# Wifinfo.net
KiCad netlist of a schematic drawn in EAGLE
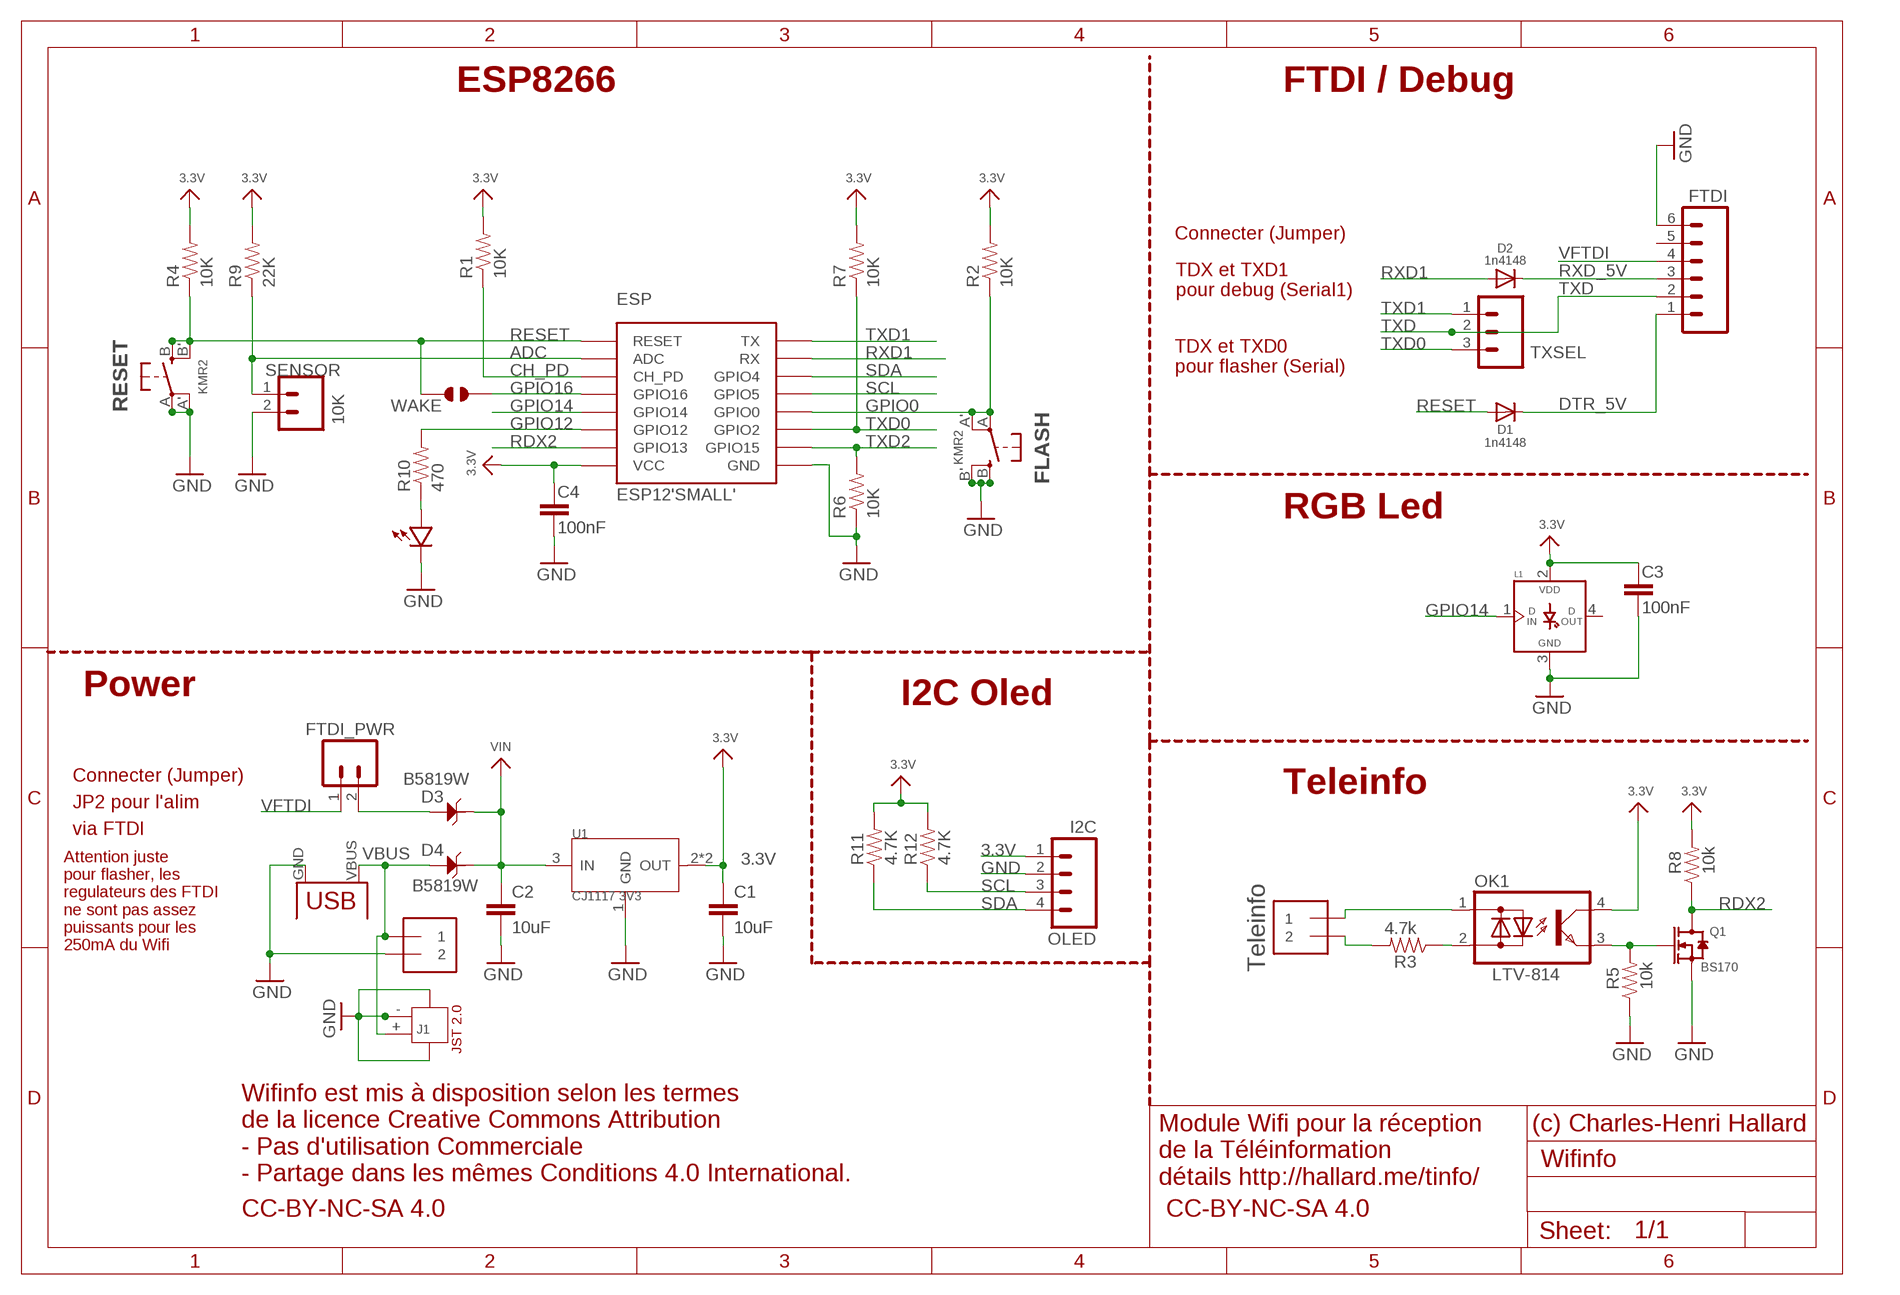
[diagram p0: schematic, sheet 1]

(export (version "E")
  (design (tool "Eeschema 10.0.6"))
  (components
    (comp (ref "C1")
      (value "10uF")
      (footprint "eagle-import:0805-CAP")
      (libsource (lib "eagle-import") (part "CAP0805-CAP"))
    )
    (comp (ref "C2")
      (value "10uF")
      (footprint "eagle-import:0805-CAP")
      (libsource (lib "eagle-import") (part "CAP0805-CAP"))
    )
    (comp (ref "C3")
      (value "100nF")
      (footprint "eagle-import:0603-CAP")
      (libsource (lib "eagle-import") (part "CAP0603-CAP"))
    )
    (comp (ref "C4")
      (value "100nF")
      (footprint "eagle-import:0603-CAP")
      (libsource (lib "eagle-import") (part "CAP0603-CAP"))
    )
    (comp (ref "D1")
      (value "1n4148")
      (footprint "eagle-import:SOD-323")
      (libsource (lib "eagle-import") (part "DIODESOD-323"))
    )
    (comp (ref "D2")
      (value "1n4148")
      (footprint "eagle-import:SOD-323")
      (libsource (lib "eagle-import") (part "DIODESOD-323"))
    )
    (comp (ref "D3")
      (value "B5819W")
      (footprint "eagle-import:SOD123-2.7X1.6")
      (libsource (lib "eagle-import") (part "D-ESD-2P-CESD5V0D1"))
    )
    (comp (ref "D4")
      (value "B5819W")
      (footprint "eagle-import:SOD123-2.7X1.6")
      (libsource (lib "eagle-import") (part "D-ESD-2P-CESD5V0D1"))
    )
    (comp (ref "ESP")
      (value "ESP12'SMALL'")
      (footprint "eagle-import:ESP08")
      (libsource (lib "eagle-import") (part "ESP12'SMALL'"))
    )
    (comp (ref "FLASH")
      (value "KMR2")
      (footprint "eagle-import:BTN_KMR2_4.6X2.8")
      (libsource (lib "eagle-import") (part "SWITCH_TACT_SMT4.6X2.8"))
    )
    (comp (ref "FTDI")
      (value "M06SIP_LOCK_NO_SILK")
      (footprint "eagle-import:1X06-SIP_LOCK_NOSILK")
      (libsource (lib "eagle-import") (part "M06SIP_LOCK_NO_SILK"))
    )
    (comp (ref "FTDI_PWR")
      (value "M02LOCK")
      (footprint "eagle-import:1X02_LOCK")
      (libsource (lib "eagle-import") (part "M02LOCK"))
    )
    (comp (ref "J1")
      (value "JST-2P-SMD'2.0'")
      (footprint "eagle-import:2P-SMD-2.0-90D")
      (libsource (lib "eagle-import") (part "JST-2P-SMD'2.0'"))
    )
    (comp (ref "L1")
      (value "WS2812B")
      (footprint "eagle-import:WS2812-PTH")
      (libsource (lib "eagle-import") (part "WS2812B5MM"))
    )
    (comp (ref "LED")
      (value "RED")
      (footprint "eagle-import:0603-LED")
      (libsource (lib "eagle-import") (part "LED0603"))
    )
    (comp (ref "OK1")
      (value "LTV-814")
      (footprint "eagle-import:DIL4-SMD")
      (fields (field (name "MF") "VISHAY/TELEFUNKEN") (field (name "MPN") "SFH6206-3"))
      (libsource (lib "eagle-import") (part "SFH6206"))
    )
    (comp (ref "OLED")
      (value "I2C")
      (footprint "eagle-import:1X04_LOCK")
      (libsource (lib "eagle-import") (part "M04LOCK"))
    )
    (comp (ref "PWR")
      (value "1X2-3.5MM")
      (footprint "eagle-import:1X2-3.5MM")
      (libsource (lib "eagle-import") (part "1X2-3.5MM"))
    )
    (comp (ref "Q1")
      (value "BS170")
      (footprint "eagle-import:SOT23")
      (libsource (lib "eagle-import") (part "MOSFET-N-''"))
    )
    (comp (ref "R1")
      (value "10K")
      (footprint "eagle-import:0603-RES")
      (libsource (lib "eagle-import") (part "RESISTOR0603-RES"))
    )
    (comp (ref "R2")
      (value "10K")
      (footprint "eagle-import:0603-RES")
      (libsource (lib "eagle-import") (part "RESISTOR0603-RES"))
    )
    (comp (ref "R3")
      (value "4.7k")
      (footprint "eagle-import:0603-RES")
      (libsource (lib "eagle-import") (part "RESISTOR0603-RES"))
    )
    (comp (ref "R4")
      (value "10K")
      (footprint "eagle-import:0603-RES")
      (libsource (lib "eagle-import") (part "RESISTOR0603-RES"))
    )
    (comp (ref "R5")
      (value "10k")
      (footprint "eagle-import:0603-RES")
      (libsource (lib "eagle-import") (part "RESISTOR0603-RES"))
    )
    (comp (ref "R6")
      (value "10K")
      (footprint "eagle-import:0603-RES")
      (libsource (lib "eagle-import") (part "RESISTOR0603-RES"))
    )
    (comp (ref "R7")
      (value "10K")
      (footprint "eagle-import:0603-RES")
      (libsource (lib "eagle-import") (part "RESISTOR0603-RES"))
    )
    (comp (ref "R8")
      (value "10k")
      (footprint "eagle-import:0603-RES")
      (libsource (lib "eagle-import") (part "RESISTOR0603-RES"))
    )
    (comp (ref "R9")
      (value "22K")
      (footprint "eagle-import:0805-RES")
      (libsource (lib "eagle-import") (part "RESISTOR0805-RES"))
    )
    (comp (ref "R10")
      (value "470")
      (footprint "eagle-import:0603-RES")
      (libsource (lib "eagle-import") (part "RESISTOR0603-RES"))
    )
    (comp (ref "R11")
      (value "4.7K")
      (footprint "eagle-import:0603-RES")
      (libsource (lib "eagle-import") (part "RESISTOR0603-RES"))
    )
    (comp (ref "R12")
      (value "4.7K")
      (footprint "eagle-import:0603-RES")
      (libsource (lib "eagle-import") (part "RESISTOR0603-RES"))
    )
    (comp (ref "RESET")
      (value "KMR2")
      (footprint "eagle-import:BTN_KMR2_4.6X2.8")
      (libsource (lib "eagle-import") (part "SWITCH_TACT_SMT4.6X2.8"))
    )
    (comp (ref "SENSOR")
      (value "10K")
      (footprint "eagle-import:1X02")
      (libsource (lib "eagle-import") (part "M02PTH"))
    )
    (comp (ref "TINFO")
      (value "1X2-3.5MM")
      (footprint "eagle-import:1X2-3.5MM")
      (libsource (lib "eagle-import") (part "1X2-3.5MM"))
    )
    (comp (ref "TXSEL")
      (value "M03LOCK")
      (footprint "eagle-import:1X03_LOCK")
      (libsource (lib "eagle-import") (part "M03LOCK"))
    )
    (comp (ref "U1")
      (value "CJ1117 3V3")
      (footprint "eagle-import:SOT89")
      (libsource (lib "eagle-import") (part "CJ1117-3.3-1310120P1"))
    )
    (comp (ref "USB")
      (value "USB")
      (footprint "eagle-import:USB_MINIB_POWER")
      (libsource (lib "eagle-import") (part "USB_POWER"))
    )
    (comp (ref "WAKE")
      (value "JUMPER_SOLDER_1X2")
      (footprint "eagle-import:JUMPER_SOLDER_1X2")
      (libsource (lib "eagle-import") (part "JUMPER_SOLDER_1X2"))
    )
  )
  (nets
    (net (code "1") (name "/ADC") (class "Default")
      (node (ref "ESP") (pin "ADC") (pinfunction "ADC_ADC") (pintype "bidirectional"))
      (node (ref "R9") (pin "1") (pinfunction "1_1") (pintype "passive"))
      (node (ref "SENSOR") (pin "1") (pinfunction "1_1") (pintype "passive"))
    )
    (net (code "2") (name "/CH_PD") (class "Default")
      (node (ref "ESP") (pin "CH_PD") (pinfunction "CH_PD_CH_PD") (pintype "bidirectional"))
      (node (ref "R1") (pin "1") (pinfunction "1_1") (pintype "passive"))
    )
    (net (code "3") (name "/DTR_5V") (class "Default")
      (node (ref "D1") (pin "C") (pinfunction "C_C") (pintype "passive"))
      (node (ref "FTDI") (pin "1") (pinfunction "1_1") (pintype "passive"))
    )
    (net (code "4") (name "/GPIO0") (class "Default")
      (node (ref "ESP") (pin "GPIO0") (pinfunction "GPIO0_GPIO0") (pintype "bidirectional"))
      (node (ref "FLASH") (pin "A") (pinfunction "P_A") (pintype "passive"))
      (node (ref "FLASH") (pin "A'") (pinfunction "P1_A'") (pintype "passive"))
      (node (ref "R2") (pin "1") (pinfunction "1_1") (pintype "passive"))
    )
    (net (code "5") (name "/GPIO12") (class "Default")
      (node (ref "ESP") (pin "GPIO12") (pinfunction "GPIO12_GPIO12") (pintype "bidirectional"))
      (node (ref "R10") (pin "2") (pinfunction "2_2") (pintype "passive"))
    )
    (net (code "6") (name "/GPIO14") (class "Default")
      (node (ref "ESP") (pin "GPIO14") (pinfunction "GPIO14_GPIO14") (pintype "bidirectional"))
      (node (ref "L1") (pin "1") (pinfunction "DIN_1") (pintype "input"))
    )
    (net (code "7") (name "/GPIO16") (class "Default")
      (node (ref "ESP") (pin "GPIO16") (pinfunction "GPIO16_GPIO16") (pintype "bidirectional"))
      (node (ref "WAKE") (pin "2") (pinfunction "2_2") (pintype "passive"))
    )
    (net (code "8") (name "/RDX2") (class "Default")
      (node (ref "ESP") (pin "GPIO13") (pinfunction "GPIO13_GPIO13") (pintype "bidirectional"))
      (node (ref "Q1") (pin "3") (pinfunction "D_3") (pintype "passive"))
      (node (ref "R8") (pin "1") (pinfunction "1_1") (pintype "passive"))
    )
    (net (code "9") (name "/RESET") (class "Default")
      (node (ref "D1") (pin "A") (pinfunction "A_A") (pintype "passive"))
      (node (ref "ESP") (pin "RESET") (pinfunction "RESET_RESET") (pintype "bidirectional"))
      (node (ref "R4") (pin "1") (pinfunction "1_1") (pintype "passive"))
      (node (ref "RESET") (pin "B") (pinfunction "S_B") (pintype "passive"))
      (node (ref "RESET") (pin "B'") (pinfunction "S1_B'") (pintype "passive"))
      (node (ref "WAKE") (pin "1") (pinfunction "1_1") (pintype "passive"))
    )
    (net (code "10") (name "/RXD1") (class "Default")
      (node (ref "D2") (pin "A") (pinfunction "A_A") (pintype "passive"))
      (node (ref "ESP") (pin "RX") (pinfunction "RX_RX") (pintype "bidirectional"))
    )
    (net (code "11") (name "/RXD_5V") (class "Default")
      (node (ref "D2") (pin "C") (pinfunction "C_C") (pintype "passive"))
      (node (ref "FTDI") (pin "3") (pinfunction "3_3") (pintype "passive"))
    )
    (net (code "12") (name "/SCL") (class "Default")
      (node (ref "ESP") (pin "GPIO5") (pinfunction "GPIO5_GPIO5") (pintype "bidirectional"))
      (node (ref "OLED") (pin "3") (pinfunction "3_3") (pintype "passive"))
      (node (ref "R12") (pin "1") (pinfunction "1_1") (pintype "passive"))
    )
    (net (code "13") (name "/SDA") (class "Default")
      (node (ref "ESP") (pin "GPIO4") (pinfunction "GPIO4_GPIO4") (pintype "bidirectional"))
      (node (ref "OLED") (pin "4") (pinfunction "4_4") (pintype "passive"))
      (node (ref "R11") (pin "1") (pinfunction "1_1") (pintype "passive"))
    )
    (net (code "14") (name "/TXD") (class "Default")
      (node (ref "FTDI") (pin "2") (pinfunction "2_2") (pintype "passive"))
      (node (ref "TXSEL") (pin "2") (pinfunction "2_2") (pintype "passive"))
    )
    (net (code "15") (name "/TXD0") (class "Default")
      (node (ref "ESP") (pin "GPIO2") (pinfunction "GPIO2_GPIO2") (pintype "bidirectional"))
      (node (ref "R7") (pin "1") (pinfunction "1_1") (pintype "passive"))
      (node (ref "TXSEL") (pin "3") (pinfunction "3_3") (pintype "passive"))
    )
    (net (code "16") (name "/TXD1") (class "Default")
      (node (ref "ESP") (pin "TX") (pinfunction "TX_TX") (pintype "bidirectional"))
      (node (ref "TXSEL") (pin "1") (pinfunction "1_1") (pintype "passive"))
    )
    (net (code "17") (name "/TXD2") (class "Default")
      (node (ref "ESP") (pin "GPIO15") (pinfunction "GPIO15_GPIO15") (pintype "bidirectional"))
      (node (ref "R6") (pin "2") (pinfunction "2_2") (pintype "passive"))
    )
    (net (code "18") (name "/VBUS") (class "Default")
      (node (ref "D4") (pin "1") (pinfunction "1_1") (pintype "bidirectional"))
      (node (ref "J1") (pin "+") (pinfunction "1_+") (pintype "bidirectional"))
      (node (ref "PWR") (pin "1") (pinfunction "1_1") (pintype "passive"))
      (node (ref "USB") (pin "VBUS") (pinfunction "VCC_VBUS") (pintype "bidirectional"))
    )
    (net (code "19") (name "/VFTDI") (class "Default")
      (node (ref "FTDI") (pin "4") (pinfunction "4_4") (pintype "passive"))
      (node (ref "FTDI_PWR") (pin "1") (pinfunction "1_1") (pintype "passive"))
    )
    (net (code "20") (name "3.3V") (class "Default")
      (node (ref "C1") (pin "1") (pinfunction "1_1") (pintype "passive"))
      (node (ref "C3") (pin "2") (pinfunction "2_2") (pintype "passive"))
      (node (ref "C4") (pin "2") (pinfunction "2_2") (pintype "passive"))
      (node (ref "ESP") (pin "VCC") (pinfunction "VCC_VCC") (pintype "bidirectional"))
      (node (ref "L1") (pin "2") (pinfunction "VDD_2") (pintype "power_in"))
      (node (ref "OK1") (pin "4") (pinfunction "C_4") (pintype "passive"))
      (node (ref "OLED") (pin "1") (pinfunction "1_1") (pintype "passive"))
      (node (ref "R1") (pin "2") (pinfunction "2_2") (pintype "passive"))
      (node (ref "R11") (pin "2") (pinfunction "2_2") (pintype "passive"))
      (node (ref "R12") (pin "2") (pinfunction "2_2") (pintype "passive"))
      (node (ref "R2") (pin "2") (pinfunction "2_2") (pintype "passive"))
      (node (ref "R4") (pin "2") (pinfunction "2_2") (pintype "passive"))
      (node (ref "R7") (pin "2") (pinfunction "2_2") (pintype "passive"))
      (node (ref "R8") (pin "2") (pinfunction "2_2") (pintype "passive"))
      (node (ref "R9") (pin "2") (pinfunction "2_2") (pintype "passive"))
      (node (ref "U1") (pin "2") (pinfunction "OUT_2") (pintype "bidirectional"))
      (node (ref "U1") (pin "4") (pinfunction "OUT_4") (pintype "bidirectional"))
    )
    (net (code "21") (name "GND") (class "Default")
      (node (ref "C1") (pin "2") (pinfunction "2_2") (pintype "passive"))
      (node (ref "C2") (pin "2") (pinfunction "2_2") (pintype "passive"))
      (node (ref "C3") (pin "1") (pinfunction "1_1") (pintype "passive"))
      (node (ref "C4") (pin "1") (pinfunction "1_1") (pintype "passive"))
      (node (ref "ESP") (pin "GND") (pinfunction "GND_GND") (pintype "bidirectional"))
      (node (ref "FLASH") (pin "B") (pinfunction "S_B") (pintype "passive"))
      (node (ref "FLASH") (pin "B'") (pinfunction "S1_B'") (pintype "passive"))
      (node (ref "FTDI") (pin "6") (pinfunction "6_6") (pintype "passive"))
      (node (ref "J1") (pin "-") (pinfunction "2_-") (pintype "bidirectional"))
      (node (ref "J1") (pin "3") (pinfunction "3_3") (pintype "bidirectional"))
      (node (ref "J1") (pin "4") (pinfunction "4_4") (pintype "bidirectional"))
      (node (ref "L1") (pin "3") (pinfunction "GND_3") (pintype "power_in"))
      (node (ref "LED") (pin "MINUS") (pinfunction "MINUS_MINUS") (pintype "passive"))
      (node (ref "OLED") (pin "2") (pinfunction "2_2") (pintype "passive"))
      (node (ref "PWR") (pin "2") (pinfunction "2_2") (pintype "passive"))
      (node (ref "Q1") (pin "2") (pinfunction "S_2") (pintype "passive"))
      (node (ref "R5") (pin "1") (pinfunction "1_1") (pintype "passive"))
      (node (ref "R6") (pin "1") (pinfunction "1_1") (pintype "passive"))
      (node (ref "RESET") (pin "A") (pinfunction "P_A") (pintype "passive"))
      (node (ref "RESET") (pin "A'") (pinfunction "P1_A'") (pintype "passive"))
      (node (ref "SENSOR") (pin "2") (pinfunction "2_2") (pintype "passive"))
      (node (ref "U1") (pin "1") (pinfunction "GND_1") (pintype "bidirectional"))
      (node (ref "USB") (pin "GND") (pinfunction "GND_GND") (pintype "bidirectional"))
    )
    (net (code "22") (name "Net-(D3-Pad1)") (class "Default")
      (node (ref "D3") (pin "1") (pinfunction "1_1") (pintype "bidirectional"))
      (node (ref "FTDI_PWR") (pin "2") (pinfunction "2_2") (pintype "passive"))
    )
    (net (code "23") (name "Net-(LED-PadPLUS)") (class "Default")
      (node (ref "LED") (pin "PLUS") (pinfunction "PLUS_PLUS") (pintype "passive"))
      (node (ref "R10") (pin "1") (pinfunction "1_1") (pintype "passive"))
    )
    (net (code "24") (name "Net-(OK1-AC1)") (class "Default")
      (node (ref "OK1") (pin "1") (pinfunction "AC1_1") (pintype "passive"))
      (node (ref "TINFO") (pin "1") (pinfunction "1_1") (pintype "passive"))
    )
    (net (code "25") (name "Net-(OK1-AC2)") (class "Default")
      (node (ref "OK1") (pin "2") (pinfunction "AC2_2") (pintype "passive"))
      (node (ref "R3") (pin "1") (pinfunction "1_1") (pintype "passive"))
    )
    (net (code "26") (name "Net-(OK1-E)") (class "Default")
      (node (ref "OK1") (pin "3") (pinfunction "E_3") (pintype "passive"))
      (node (ref "Q1") (pin "1") (pinfunction "G_1") (pintype "passive"))
      (node (ref "R5") (pin "2") (pinfunction "2_2") (pintype "passive"))
    )
    (net (code "27") (name "Net-(R3-Pad2)") (class "Default")
      (node (ref "R3") (pin "2") (pinfunction "2_2") (pintype "passive"))
      (node (ref "TINFO") (pin "2") (pinfunction "2_2") (pintype "passive"))
    )
    (net (code "28") (name "VIN") (class "Default")
      (node (ref "C2") (pin "1") (pinfunction "1_1") (pintype "passive"))
      (node (ref "D3") (pin "2") (pinfunction "2_2") (pintype "bidirectional"))
      (node (ref "D4") (pin "2") (pinfunction "2_2") (pintype "bidirectional"))
      (node (ref "U1") (pin "3") (pinfunction "IN_3") (pintype "bidirectional"))
    )
    (net (code "29") (name "unconnected-(FTDI-Pad5)") (class "Default")
      (node (ref "FTDI") (pin "5") (pinfunction "5_5") (pintype "passive"))
    )
    (net (code "30") (name "unconnected-(L1-DOUT-Pad4)") (class "Default")
      (node (ref "L1") (pin "4") (pinfunction "DOUT_4") (pintype "output"))
    )
  )
)
